# stm32breakout.net
KiCad netlist of a schematic drawn in EAGLE
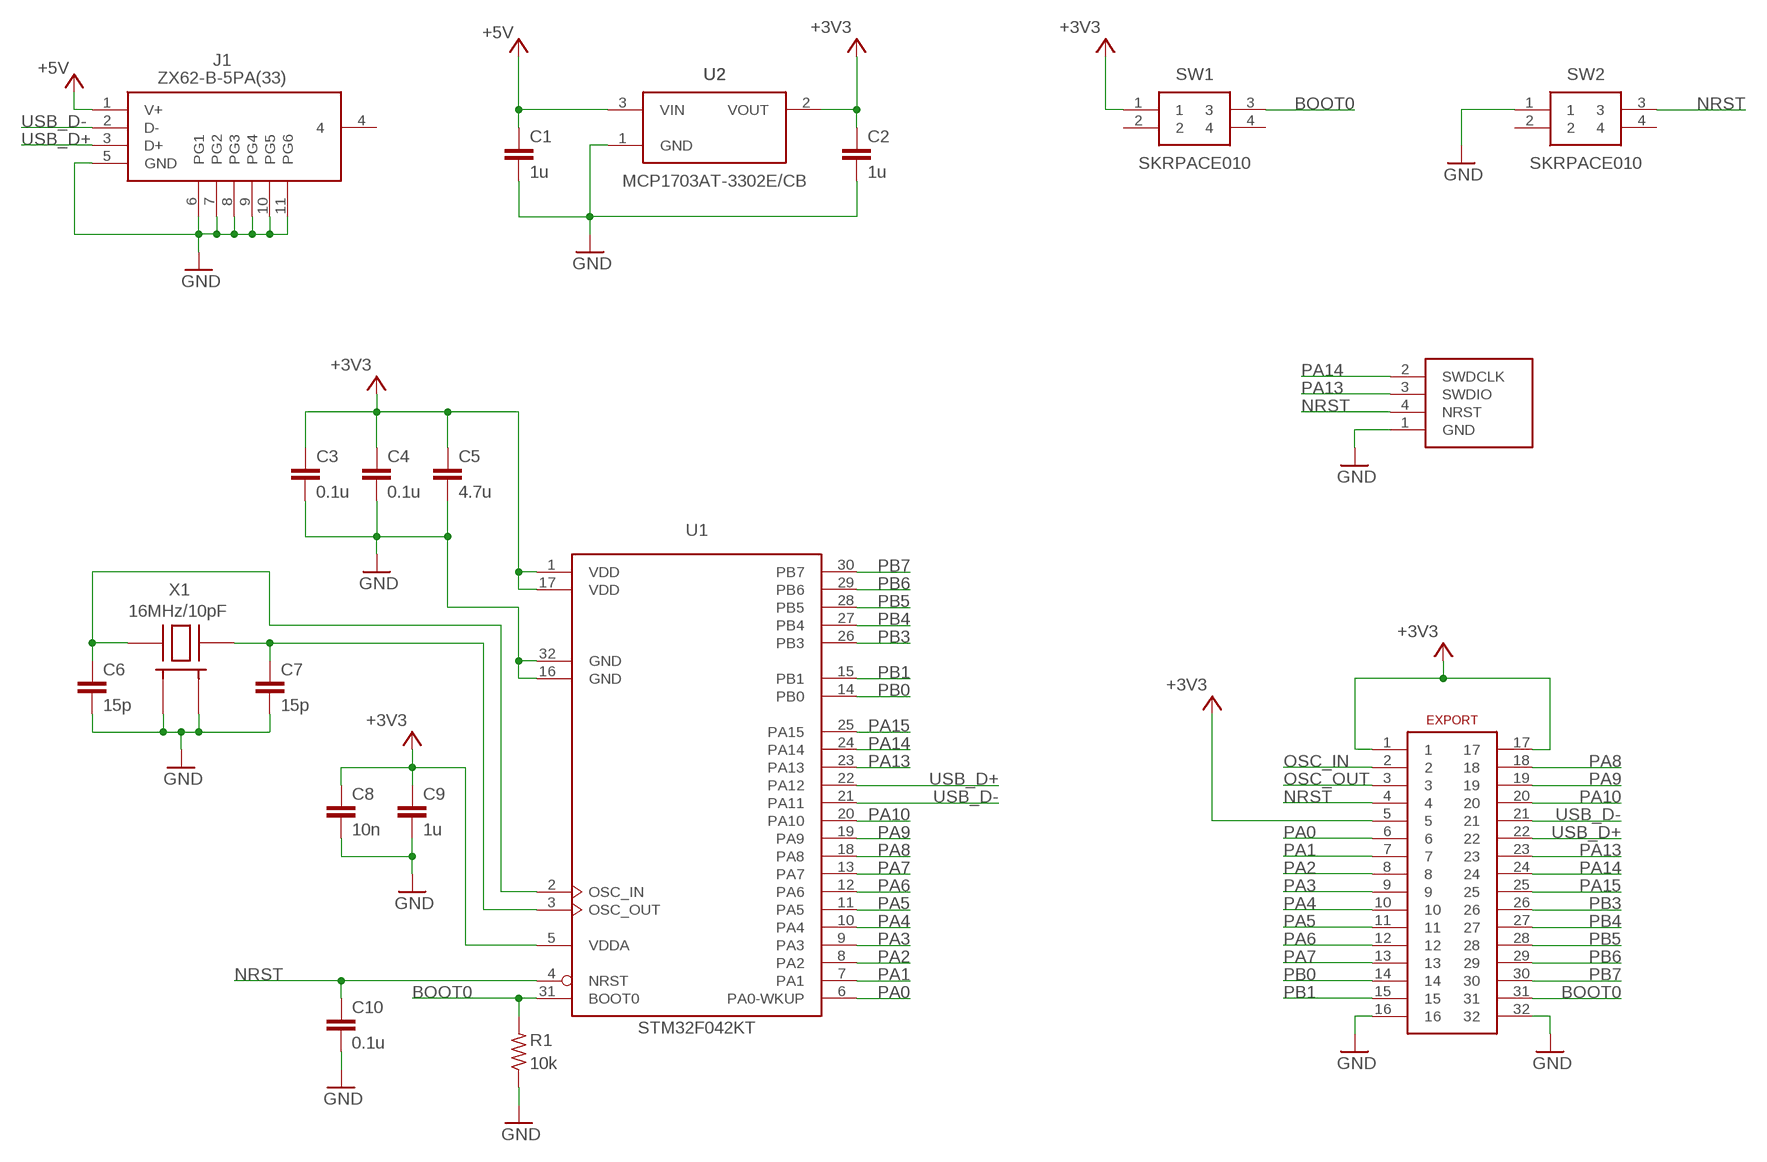
[diagram p0: schematic, sheet 1]

(export (version "E")
  (design (tool "Eeschema 10.0.6"))
  (components
    (comp (ref "C1")
      (value "1u")
      (footprint "eagle-import:RCL_C0402_HS")
      (libsource (lib "eagle-import") (part "RCL_C-EUC0402-HS"))
    )
    (comp (ref "C2")
      (value "1u")
      (footprint "eagle-import:RCL_C0402_HS")
      (libsource (lib "eagle-import") (part "RCL_C-EUC0402-HS"))
    )
    (comp (ref "C3")
      (value "0.1u")
      (footprint "eagle-import:RCL_C0402_HS")
      (libsource (lib "eagle-import") (part "RCL_C-EUC0402-HS"))
    )
    (comp (ref "C4")
      (value "0.1u")
      (footprint "eagle-import:RCL_C0402_HS")
      (libsource (lib "eagle-import") (part "RCL_C-EUC0402-HS"))
    )
    (comp (ref "C5")
      (value "4.7u")
      (footprint "eagle-import:RCL_C0402_HS")
      (libsource (lib "eagle-import") (part "RCL_C-EUC0402-HS"))
    )
    (comp (ref "C6")
      (value "15p")
      (footprint "eagle-import:RCL_C0402_HS")
      (libsource (lib "eagle-import") (part "RCL_C-EUC0402-HS"))
    )
    (comp (ref "C7")
      (value "15p")
      (footprint "eagle-import:RCL_C0402_HS")
      (libsource (lib "eagle-import") (part "RCL_C-EUC0402-HS"))
    )
    (comp (ref "C8")
      (value "10n")
      (footprint "eagle-import:RCL_C0402_HS")
      (libsource (lib "eagle-import") (part "RCL_C-EUC0402-HS"))
    )
    (comp (ref "C9")
      (value "1u")
      (footprint "eagle-import:RCL_C0402_HS")
      (libsource (lib "eagle-import") (part "RCL_C-EUC0402-HS"))
    )
    (comp (ref "C10")
      (value "0.1u")
      (footprint "eagle-import:RCL_C0402_HS")
      (libsource (lib "eagle-import") (part "RCL_C-EUC0402-HS"))
    )
    (comp (ref "EXPORT")
      (value "2X16PIN")
      (footprint "eagle-import:2X16PIN")
      (libsource (lib "eagle-import") (part "2X16PIN"))
    )
    (comp (ref "J1")
      (value "ZX62-B-5PA(33)")
      (footprint "eagle-import:ZX62-B-5PA(33)-TRUE-HANDSOLD")
      (libsource (lib "eagle-import") (part "ZX62-B-5PA(33)-FULL"))
    )
    (comp (ref "R1")
      (value "10k")
      (footprint "eagle-import:RCL_R0402_HS")
      (libsource (lib "eagle-import") (part "RCL_R-US_R0402-HS"))
    )
    (comp (ref "SW1")
      (value "SKRPACE010")
      (footprint "eagle-import:SMT(4.2X3.2)")
      (libsource (lib "eagle-import") (part "SKRPACE010"))
    )
    (comp (ref "SW2")
      (value "SKRPACE010")
      (footprint "eagle-import:SMT(4.2X3.2)")
      (libsource (lib "eagle-import") (part "SKRPACE010"))
    )
    (comp (ref "U$1")
      (value "4PIN-DEBUG")
      (footprint "eagle-import:4PIN-DEBUG")
      (libsource (lib "eagle-import") (part "4PIN-DEBUG"))
    )
    (comp (ref "U1")
      (value "STM32F042KT")
      (footprint "eagle-import:LQFP32-M")
      (libsource (lib "eagle-import") (part "STM32F042KT"))
    )
    (comp (ref "U2")
      (value "MCP1703AT-3302E/CB")
      (footprint "eagle-import:SOT23")
      (libsource (lib "eagle-import") (part "LDO-REGULATOR"))
    )
    (comp (ref "X1")
      (value "16MHz/10pF")
      (footprint "eagle-import:CRYSTAL3225-HS")
      (libsource (lib "eagle-import") (part "CRYSTAL3225HS"))
    )
  )
  (nets
    (net (code "1") (name "+3V3") (class "Default")
      (node (ref "C2") (pin "1") (pinfunction "1_1") (pintype "passive"))
      (node (ref "C3") (pin "1") (pinfunction "1_1") (pintype "passive"))
      (node (ref "C4") (pin "1") (pinfunction "1_1") (pintype "passive"))
      (node (ref "C5") (pin "1") (pinfunction "1_1") (pintype "passive"))
      (node (ref "C8") (pin "1") (pinfunction "1_1") (pintype "passive"))
      (node (ref "C9") (pin "1") (pinfunction "1_1") (pintype "passive"))
      (node (ref "EXPORT") (pin "1") (pinfunction "1_1") (pintype "bidirectional"))
      (node (ref "EXPORT") (pin "17") (pinfunction "17_17") (pintype "bidirectional"))
      (node (ref "EXPORT") (pin "5") (pinfunction "5_5") (pintype "bidirectional"))
      (node (ref "SW1") (pin "1") (pinfunction "1_1") (pintype "bidirectional"))
      (node (ref "U1") (pin "1") (pinfunction "VDD_1") (pintype "power_in"))
      (node (ref "U1") (pin "17") (pinfunction "VDD_17") (pintype "power_in"))
      (node (ref "U1") (pin "5") (pinfunction "VDDA_5") (pintype "power_in"))
      (node (ref "U2") (pin "2") (pinfunction "VOUT_2") (pintype "bidirectional"))
    )
    (net (code "2") (name "+5V") (class "Default")
      (node (ref "C1") (pin "1") (pinfunction "1_1") (pintype "passive"))
      (node (ref "J1") (pin "1") (pinfunction "V+_1") (pintype "bidirectional"))
      (node (ref "U2") (pin "3") (pinfunction "VIN_3") (pintype "bidirectional"))
    )
    (net (code "3") (name "/BOOT0") (class "Default")
      (node (ref "EXPORT") (pin "31") (pinfunction "31_31") (pintype "bidirectional"))
      (node (ref "R1") (pin "2") (pinfunction "2_2") (pintype "passive"))
      (node (ref "SW1") (pin "3") (pinfunction "3_3") (pintype "bidirectional"))
      (node (ref "U1") (pin "31") (pinfunction "BOOT0_31") (pintype "input"))
    )
    (net (code "4") (name "/NRST") (class "Default")
      (node (ref "C10") (pin "1") (pinfunction "1_1") (pintype "passive"))
      (node (ref "EXPORT") (pin "4") (pinfunction "4_4") (pintype "bidirectional"))
      (node (ref "SW2") (pin "3") (pinfunction "3_3") (pintype "bidirectional"))
      (node (ref "U$1") (pin "4") (pinfunction "NRST_4") (pintype "bidirectional"))
      (node (ref "U1") (pin "4") (pinfunction "NRST_4") (pintype "bidirectional"))
    )
    (net (code "5") (name "/OSC_IN") (class "Default")
      (node (ref "C6") (pin "1") (pinfunction "1_1") (pintype "passive"))
      (node (ref "EXPORT") (pin "2") (pinfunction "2_2") (pintype "bidirectional"))
      (node (ref "U1") (pin "2") (pinfunction "OSC_IN_2") (pintype "bidirectional"))
      (node (ref "X1") (pin "1") (pinfunction "HOT_1_1") (pintype "bidirectional"))
    )
    (net (code "6") (name "/OSC_OUT") (class "Default")
      (node (ref "C7") (pin "1") (pinfunction "1_1") (pintype "passive"))
      (node (ref "EXPORT") (pin "3") (pinfunction "3_3") (pintype "bidirectional"))
      (node (ref "U1") (pin "3") (pinfunction "OSC_OUT_3") (pintype "bidirectional"))
      (node (ref "X1") (pin "3") (pinfunction "HOT_2_3") (pintype "bidirectional"))
    )
    (net (code "7") (name "/PA0") (class "Default")
      (node (ref "EXPORT") (pin "6") (pinfunction "6_6") (pintype "bidirectional"))
      (node (ref "U1") (pin "6") (pinfunction "PA0-WKUP_6") (pintype "bidirectional"))
    )
    (net (code "8") (name "/PA1") (class "Default")
      (node (ref "EXPORT") (pin "7") (pinfunction "7_7") (pintype "bidirectional"))
      (node (ref "U1") (pin "7") (pinfunction "PA1_7") (pintype "bidirectional"))
    )
    (net (code "9") (name "/PA2") (class "Default")
      (node (ref "EXPORT") (pin "8") (pinfunction "8_8") (pintype "bidirectional"))
      (node (ref "U1") (pin "8") (pinfunction "PA2_8") (pintype "bidirectional"))
    )
    (net (code "10") (name "/PA3") (class "Default")
      (node (ref "EXPORT") (pin "9") (pinfunction "9_9") (pintype "bidirectional"))
      (node (ref "U1") (pin "9") (pinfunction "PA3_9") (pintype "bidirectional"))
    )
    (net (code "11") (name "/PA4") (class "Default")
      (node (ref "EXPORT") (pin "10") (pinfunction "10_10") (pintype "bidirectional"))
      (node (ref "U1") (pin "10") (pinfunction "PA4_10") (pintype "bidirectional"))
    )
    (net (code "12") (name "/PA5") (class "Default")
      (node (ref "EXPORT") (pin "11") (pinfunction "11_11") (pintype "bidirectional"))
      (node (ref "U1") (pin "11") (pinfunction "PA5_11") (pintype "bidirectional"))
    )
    (net (code "13") (name "/PA6") (class "Default")
      (node (ref "EXPORT") (pin "12") (pinfunction "12_12") (pintype "bidirectional"))
      (node (ref "U1") (pin "12") (pinfunction "PA6_12") (pintype "bidirectional"))
    )
    (net (code "14") (name "/PA7") (class "Default")
      (node (ref "EXPORT") (pin "13") (pinfunction "13_13") (pintype "bidirectional"))
      (node (ref "U1") (pin "13") (pinfunction "PA7_13") (pintype "bidirectional"))
    )
    (net (code "15") (name "/PA8") (class "Default")
      (node (ref "EXPORT") (pin "18") (pinfunction "18_18") (pintype "bidirectional"))
      (node (ref "U1") (pin "18") (pinfunction "PA8_18") (pintype "bidirectional"))
    )
    (net (code "16") (name "/PA9") (class "Default")
      (node (ref "EXPORT") (pin "19") (pinfunction "19_19") (pintype "bidirectional"))
      (node (ref "U1") (pin "19") (pinfunction "PA9_19") (pintype "bidirectional"))
    )
    (net (code "17") (name "/PA10") (class "Default")
      (node (ref "EXPORT") (pin "20") (pinfunction "20_20") (pintype "bidirectional"))
      (node (ref "U1") (pin "20") (pinfunction "PA10_20") (pintype "bidirectional"))
    )
    (net (code "18") (name "/PA13") (class "Default")
      (node (ref "EXPORT") (pin "23") (pinfunction "23_23") (pintype "bidirectional"))
      (node (ref "U$1") (pin "3") (pinfunction "SWDIO_3") (pintype "bidirectional"))
      (node (ref "U1") (pin "23") (pinfunction "PA13_23") (pintype "bidirectional"))
    )
    (net (code "19") (name "/PA14") (class "Default")
      (node (ref "EXPORT") (pin "24") (pinfunction "24_24") (pintype "bidirectional"))
      (node (ref "U$1") (pin "2") (pinfunction "SWDCLK_2") (pintype "bidirectional"))
      (node (ref "U1") (pin "24") (pinfunction "PA14_24") (pintype "bidirectional"))
    )
    (net (code "20") (name "/PA15") (class "Default")
      (node (ref "EXPORT") (pin "25") (pinfunction "25_25") (pintype "bidirectional"))
      (node (ref "U1") (pin "25") (pinfunction "PA15_25") (pintype "bidirectional"))
    )
    (net (code "21") (name "/PB0") (class "Default")
      (node (ref "EXPORT") (pin "14") (pinfunction "14_14") (pintype "bidirectional"))
      (node (ref "U1") (pin "14") (pinfunction "PB0_14") (pintype "bidirectional"))
    )
    (net (code "22") (name "/PB1") (class "Default")
      (node (ref "EXPORT") (pin "15") (pinfunction "15_15") (pintype "bidirectional"))
      (node (ref "U1") (pin "15") (pinfunction "PB1_15") (pintype "bidirectional"))
    )
    (net (code "23") (name "/PB3") (class "Default")
      (node (ref "EXPORT") (pin "26") (pinfunction "26_26") (pintype "bidirectional"))
      (node (ref "U1") (pin "26") (pinfunction "PB3_26") (pintype "bidirectional"))
    )
    (net (code "24") (name "/PB4") (class "Default")
      (node (ref "EXPORT") (pin "27") (pinfunction "27_27") (pintype "bidirectional"))
      (node (ref "U1") (pin "27") (pinfunction "PB4_27") (pintype "bidirectional"))
    )
    (net (code "25") (name "/PB5") (class "Default")
      (node (ref "EXPORT") (pin "28") (pinfunction "28_28") (pintype "bidirectional"))
      (node (ref "U1") (pin "28") (pinfunction "PB5_28") (pintype "bidirectional"))
    )
    (net (code "26") (name "/PB6") (class "Default")
      (node (ref "EXPORT") (pin "29") (pinfunction "29_29") (pintype "bidirectional"))
      (node (ref "U1") (pin "29") (pinfunction "PB6_29") (pintype "bidirectional"))
    )
    (net (code "27") (name "/PB7") (class "Default")
      (node (ref "EXPORT") (pin "30") (pinfunction "30_30") (pintype "bidirectional"))
      (node (ref "U1") (pin "30") (pinfunction "PB7_30") (pintype "bidirectional"))
    )
    (net (code "28") (name "/USB_D+") (class "Default")
      (node (ref "EXPORT") (pin "22") (pinfunction "22_22") (pintype "bidirectional"))
      (node (ref "J1") (pin "3") (pinfunction "D+_3") (pintype "bidirectional"))
      (node (ref "U1") (pin "22") (pinfunction "PA12_22") (pintype "bidirectional"))
    )
    (net (code "29") (name "/USB_D-") (class "Default")
      (node (ref "EXPORT") (pin "21") (pinfunction "21_21") (pintype "bidirectional"))
      (node (ref "J1") (pin "2") (pinfunction "D-_2") (pintype "bidirectional"))
      (node (ref "U1") (pin "21") (pinfunction "PA11_21") (pintype "bidirectional"))
    )
    (net (code "30") (name "GND") (class "Default")
      (node (ref "C1") (pin "2") (pinfunction "2_2") (pintype "passive"))
      (node (ref "C10") (pin "2") (pinfunction "2_2") (pintype "passive"))
      (node (ref "C2") (pin "2") (pinfunction "2_2") (pintype "passive"))
      (node (ref "C3") (pin "2") (pinfunction "2_2") (pintype "passive"))
      (node (ref "C4") (pin "2") (pinfunction "2_2") (pintype "passive"))
      (node (ref "C5") (pin "2") (pinfunction "2_2") (pintype "passive"))
      (node (ref "C6") (pin "2") (pinfunction "2_2") (pintype "passive"))
      (node (ref "C7") (pin "2") (pinfunction "2_2") (pintype "passive"))
      (node (ref "C8") (pin "2") (pinfunction "2_2") (pintype "passive"))
      (node (ref "C9") (pin "2") (pinfunction "2_2") (pintype "passive"))
      (node (ref "EXPORT") (pin "16") (pinfunction "16_16") (pintype "bidirectional"))
      (node (ref "EXPORT") (pin "32") (pinfunction "32_32") (pintype "bidirectional"))
      (node (ref "J1") (pin "10") (pinfunction "PG5_10") (pintype "bidirectional"))
      (node (ref "J1") (pin "11") (pinfunction "PG6_11") (pintype "bidirectional"))
      (node (ref "J1") (pin "5") (pinfunction "GND_5") (pintype "bidirectional"))
      (node (ref "J1") (pin "6") (pinfunction "PG1_6") (pintype "bidirectional"))
      (node (ref "J1") (pin "7") (pinfunction "PG2_7") (pintype "bidirectional"))
      (node (ref "J1") (pin "8") (pinfunction "PG3_8") (pintype "bidirectional"))
      (node (ref "J1") (pin "9") (pinfunction "PG4_9") (pintype "bidirectional"))
      (node (ref "R1") (pin "1") (pinfunction "1_1") (pintype "passive"))
      (node (ref "SW2") (pin "1") (pinfunction "1_1") (pintype "bidirectional"))
      (node (ref "U$1") (pin "1") (pinfunction "GND_1") (pintype "bidirectional"))
      (node (ref "U1") (pin "16") (pinfunction "GND_16") (pintype "power_in"))
      (node (ref "U1") (pin "32") (pinfunction "GND_32") (pintype "power_in"))
      (node (ref "U2") (pin "1") (pinfunction "GND_1") (pintype "bidirectional"))
      (node (ref "X1") (pin "2") (pinfunction "GND_1_2") (pintype "bidirectional"))
      (node (ref "X1") (pin "4") (pinfunction "GND_2_4") (pintype "bidirectional"))
    )
    (net (code "31") (name "unconnected-(J1-Pad4)") (class "Default")
      (node (ref "J1") (pin "4") (pinfunction "4_4") (pintype "bidirectional"))
    )
    (net (code "32") (name "unconnected-(SW1-Pad2)") (class "Default")
      (node (ref "SW1") (pin "2") (pinfunction "2_2") (pintype "bidirectional"))
    )
    (net (code "33") (name "unconnected-(SW1-Pad4)") (class "Default")
      (node (ref "SW1") (pin "4") (pinfunction "4_4") (pintype "bidirectional"))
    )
    (net (code "34") (name "unconnected-(SW2-Pad2)") (class "Default")
      (node (ref "SW2") (pin "2") (pinfunction "2_2") (pintype "bidirectional"))
    )
    (net (code "35") (name "unconnected-(SW2-Pad4)") (class "Default")
      (node (ref "SW2") (pin "4") (pinfunction "4_4") (pintype "bidirectional"))
    )
  )
)
